# LB_i16-Pulse-v03_rev2.net
KiCad netlist of a schematic drawn in EAGLE
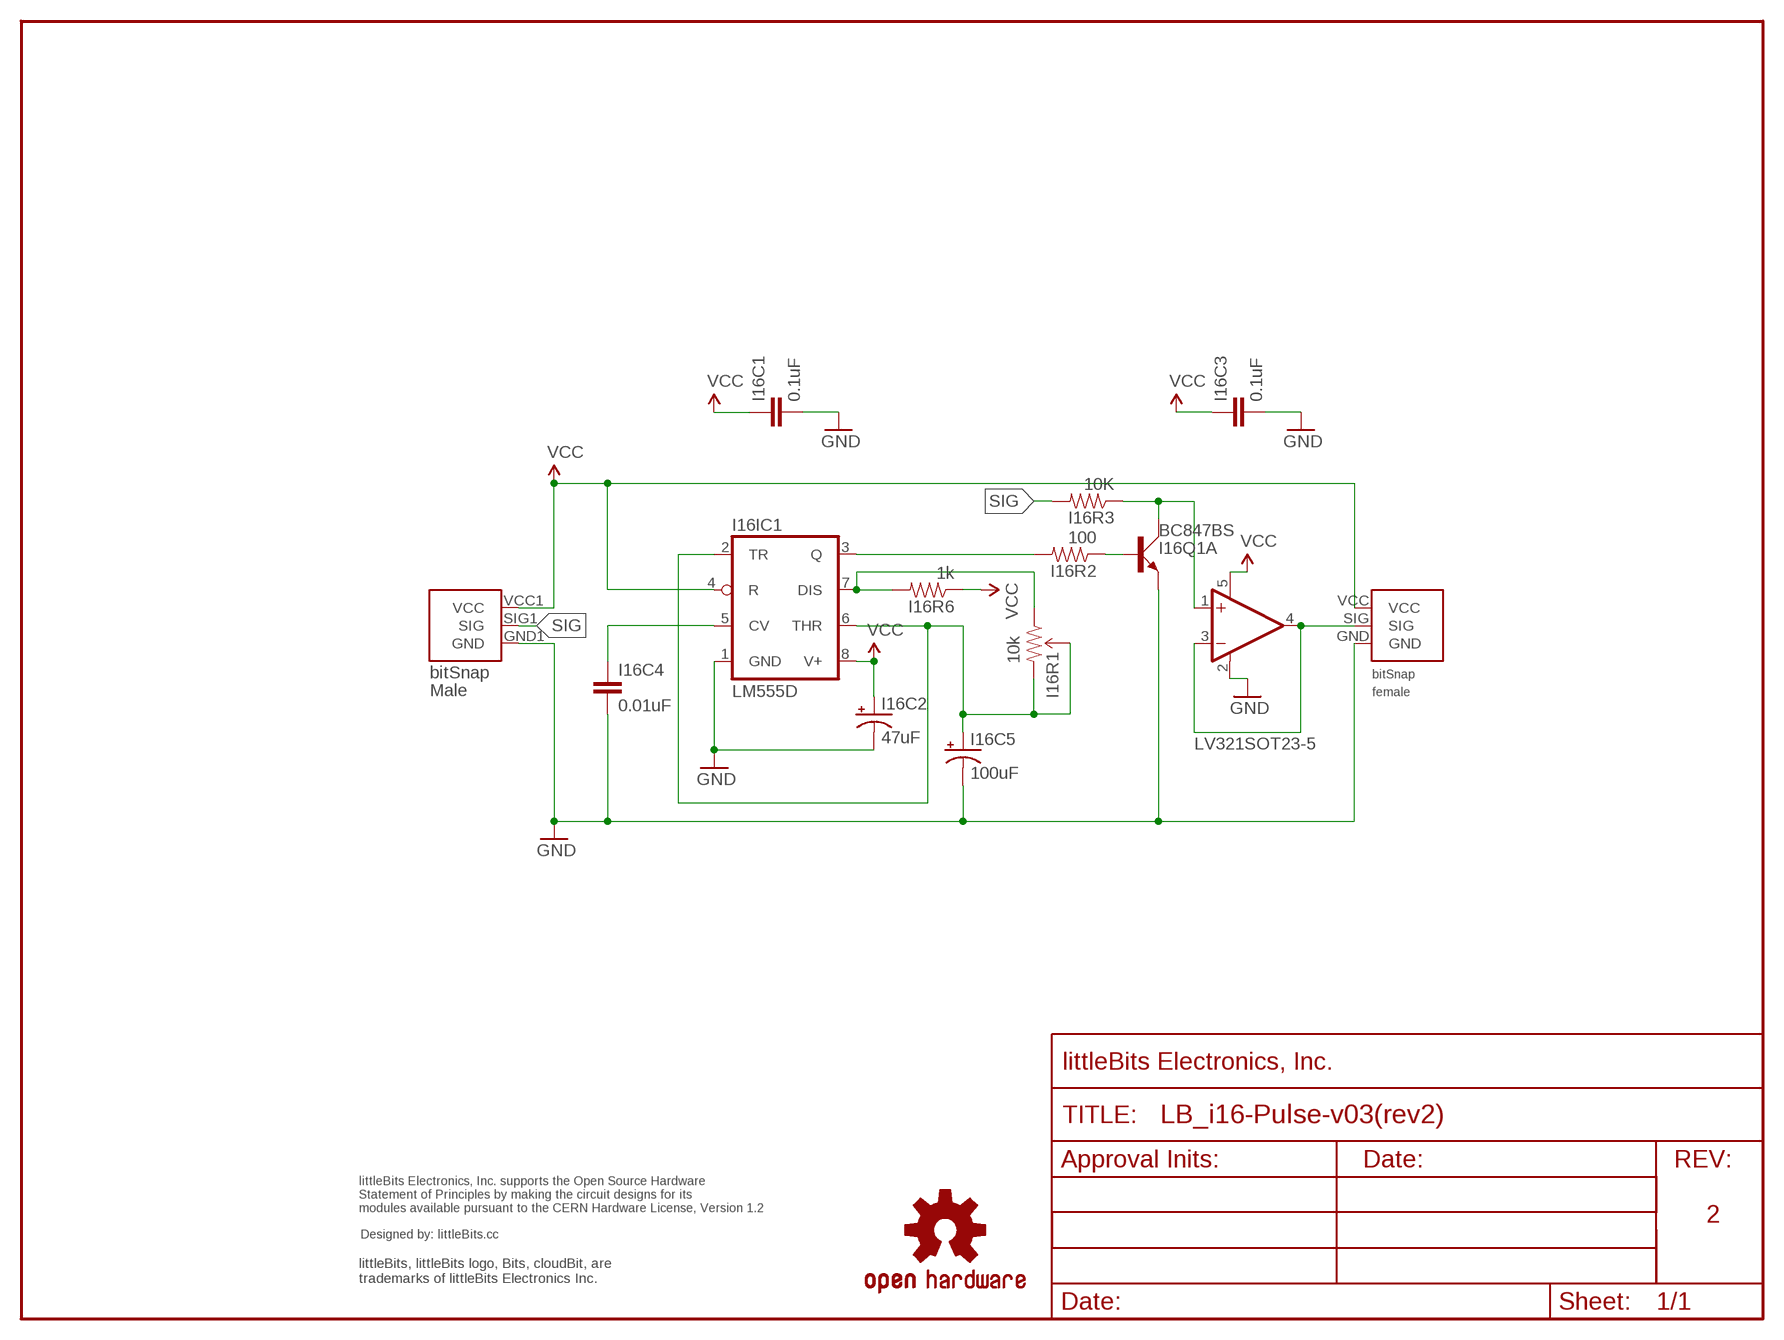
[diagram p0: schematic, sheet 1]

(export (version "E")
  (design (tool "Eeschema 10.0.6"))
  (components
    (comp (ref "I16BSF1")
      (value "BITSNAP_V03_FEMALE")
      (footprint "eagle-import:BITSNAP_V03_FEMALE")
      (libsource (lib "eagle-import") (part "BITSNAP_V03_FEMALE"))
    )
    (comp (ref "I16BSM1")
      (value "BITSNAP_V03_MALE")
      (footprint "eagle-import:BITSNAP_V03_MALE")
      (libsource (lib "eagle-import") (part "BITSNAP_V03_MALE"))
    )
    (comp (ref "I16C1")
      (value "0.1uF")
      (footprint "eagle-import:0603-CAP")
      (libsource (lib "eagle-import") (part "CAP0603-CAP"))
    )
    (comp (ref "I16C2")
      (value "47uF")
      (footprint "eagle-import:EIA3528")
      (libsource (lib "eagle-import") (part "CAP_POL3528"))
    )
    (comp (ref "I16C3")
      (value "0.1uF")
      (footprint "eagle-import:0603-CAP")
      (libsource (lib "eagle-import") (part "CAP0603-CAP"))
    )
    (comp (ref "I16C4")
      (value "0.01uF")
      (footprint "eagle-import:0603-CAP")
      (libsource (lib "eagle-import") (part "CAP0603-CAP"))
    )
    (comp (ref "I16C5")
      (value "100uF")
      (footprint "eagle-import:EIA6032")
      (libsource (lib "eagle-import") (part "CAP_POL6032"))
    )
    (comp (ref "I16IC1")
      (value "LM555D")
      (footprint "eagle-import:SO08")
      (libsource (lib "eagle-import") (part "555DLM"))
    )
    (comp (ref "I16Q1")
      (value "BC847BS")
      (footprint "eagle-import:SOT363_PHILIPS")
      (libsource (lib "eagle-import") (part "BC847BS"))
    )
    (comp (ref "I16R1")
      (value "10k")
      (footprint "eagle-import:TRIMPOT-3MM")
      (libsource (lib "eagle-import") (part "TRIMPOTSMD"))
    )
    (comp (ref "I16R2")
      (value "100")
      (footprint "eagle-import:0603-RES")
      (libsource (lib "eagle-import") (part "RESISTOR0603-RES"))
    )
    (comp (ref "I16R3")
      (value "10K")
      (footprint "eagle-import:0603-RES")
      (libsource (lib "eagle-import") (part "RESISTOR0603-RES"))
    )
    (comp (ref "I16R6")
      (value "1k")
      (footprint "eagle-import:0603-RES")
      (libsource (lib "eagle-import") (part "RESISTOR0603-RES"))
    )
    (comp (ref "I16U3")
      (value "LV321SOT23-5")
      (footprint "eagle-import:SOT23-5")
      (libsource (lib "eagle-import") (part "LV321SOT23-5"))
    )
    (comp (ref "U$1")
      (value "OSHWCREDIT")
      (footprint "eagle-import:OSHWCREDIT")
      (libsource (lib "eagle-import") (part "OSHWCREDIT"))
    )
    (comp (ref "U$2")
      (value "FRAME-LETTER-OHWOHW")
      (footprint "eagle-import:FABDWG01-OHW")
      (libsource (lib "eagle-import") (part "FRAME-LETTER-OHWOHW"))
    )
    (comp (ref "U$3")
      (value "OSHW-LOGOL")
      (footprint "eagle-import:OSHW-LOGO-L")
      (libsource (lib "eagle-import") (part "OSHW-LOGOL"))
    )
  )
  (nets
    (net (code "1") (name "GND") (class "Default")
      (node (ref "I16BSF1") (pin "GND") (pinfunction "GND_GND") (pintype "bidirectional"))
      (node (ref "I16BSM1") (pin "GND1") (pinfunction "GND_GND1") (pintype "bidirectional"))
      (node (ref "I16C1") (pin "2") (pinfunction "2_2") (pintype "passive"))
      (node (ref "I16C2") (pin "C") (pinfunction "-_C") (pintype "passive"))
      (node (ref "I16C3") (pin "2") (pinfunction "2_2") (pintype "passive"))
      (node (ref "I16C4") (pin "2") (pinfunction "2_2") (pintype "passive"))
      (node (ref "I16C5") (pin "P$2") (pinfunction "-_P$2") (pintype "passive"))
      (node (ref "I16IC1") (pin "1") (pinfunction "GND_1") (pintype "power_in"))
      (node (ref "I16Q1") (pin "1") (pinfunction "E_1") (pintype "passive"))
      (node (ref "I16U3") (pin "2") (pinfunction "V-_2") (pintype "power_in"))
    )
    (net (code "2") (name "Net-(I16C5-+)") (class "Default")
      (node (ref "I16C5") (pin "P$1") (pinfunction "+_P$1") (pintype "passive"))
      (node (ref "I16IC1") (pin "2") (pinfunction "TR_2") (pintype "input"))
      (node (ref "I16IC1") (pin "6") (pinfunction "THR_6") (pintype "input"))
      (node (ref "I16R1") (pin "2") (pinfunction "WIPER_2") (pintype "passive"))
      (node (ref "I16R1") (pin "3") (pinfunction "CW_3") (pintype "passive"))
    )
    (net (code "3") (name "Net-(I16IC1-CV)") (class "Default")
      (node (ref "I16C4") (pin "1") (pinfunction "1_1") (pintype "passive"))
      (node (ref "I16IC1") (pin "5") (pinfunction "CV_5") (pintype "input"))
    )
    (net (code "4") (name "Net-(I16IC1-DIS)") (class "Default")
      (node (ref "I16IC1") (pin "7") (pinfunction "DIS_7") (pintype "input"))
      (node (ref "I16R1") (pin "1") (pinfunction "CCW_1") (pintype "passive"))
      (node (ref "I16R6") (pin "2") (pinfunction "2_2") (pintype "passive"))
    )
    (net (code "5") (name "Net-(I16IC1-Q)") (class "Default")
      (node (ref "I16IC1") (pin "3") (pinfunction "Q_3") (pintype "output"))
      (node (ref "I16R2") (pin "2") (pinfunction "2_2") (pintype "passive"))
    )
    (net (code "6") (name "Net-(I16Q1A-B)") (class "Default")
      (node (ref "I16Q1") (pin "2") (pinfunction "B_2") (pintype "passive"))
      (node (ref "I16R2") (pin "1") (pinfunction "1_1") (pintype "passive"))
    )
    (net (code "7") (name "Net-(I16Q1A-C)") (class "Default")
      (node (ref "I16Q1") (pin "6") (pinfunction "C_6") (pintype "passive"))
      (node (ref "I16R3") (pin "1") (pinfunction "1_1") (pintype "passive"))
      (node (ref "I16U3") (pin "1") (pinfunction "+IN_1") (pintype "input"))
    )
    (net (code "8") (name "Net-(I16U3--IN)") (class "Default")
      (node (ref "I16BSF1") (pin "SIG") (pinfunction "SIG_SIG") (pintype "bidirectional"))
      (node (ref "I16U3") (pin "3") (pinfunction "-IN_3") (pintype "input"))
      (node (ref "I16U3") (pin "4") (pinfunction "OUT_4") (pintype "output"))
    )
    (net (code "9") (name "SIG") (class "Default")
      (node (ref "I16BSM1") (pin "SIG1") (pinfunction "SIG_SIG1") (pintype "bidirectional"))
      (node (ref "I16R3") (pin "2") (pinfunction "2_2") (pintype "passive"))
    )
    (net (code "10") (name "VCC") (class "Default")
      (node (ref "I16BSF1") (pin "VCC") (pinfunction "VCC_VCC") (pintype "bidirectional"))
      (node (ref "I16BSM1") (pin "VCC1") (pinfunction "VCC_VCC1") (pintype "bidirectional"))
      (node (ref "I16C1") (pin "1") (pinfunction "1_1") (pintype "passive"))
      (node (ref "I16C2") (pin "A") (pinfunction "+_A") (pintype "passive"))
      (node (ref "I16C3") (pin "1") (pinfunction "1_1") (pintype "passive"))
      (node (ref "I16IC1") (pin "4") (pinfunction "R_4") (pintype "input"))
      (node (ref "I16IC1") (pin "8") (pinfunction "V+_8") (pintype "power_in"))
      (node (ref "I16R6") (pin "1") (pinfunction "1_1") (pintype "passive"))
      (node (ref "I16U3") (pin "5") (pinfunction "V+_5") (pintype "power_in"))
    )
  )
)
